# 84_PCIE-PCIE3_0_1x4Lanes_RC_64P.net
KiCad netlist of a schematic drawn in Altium Designer
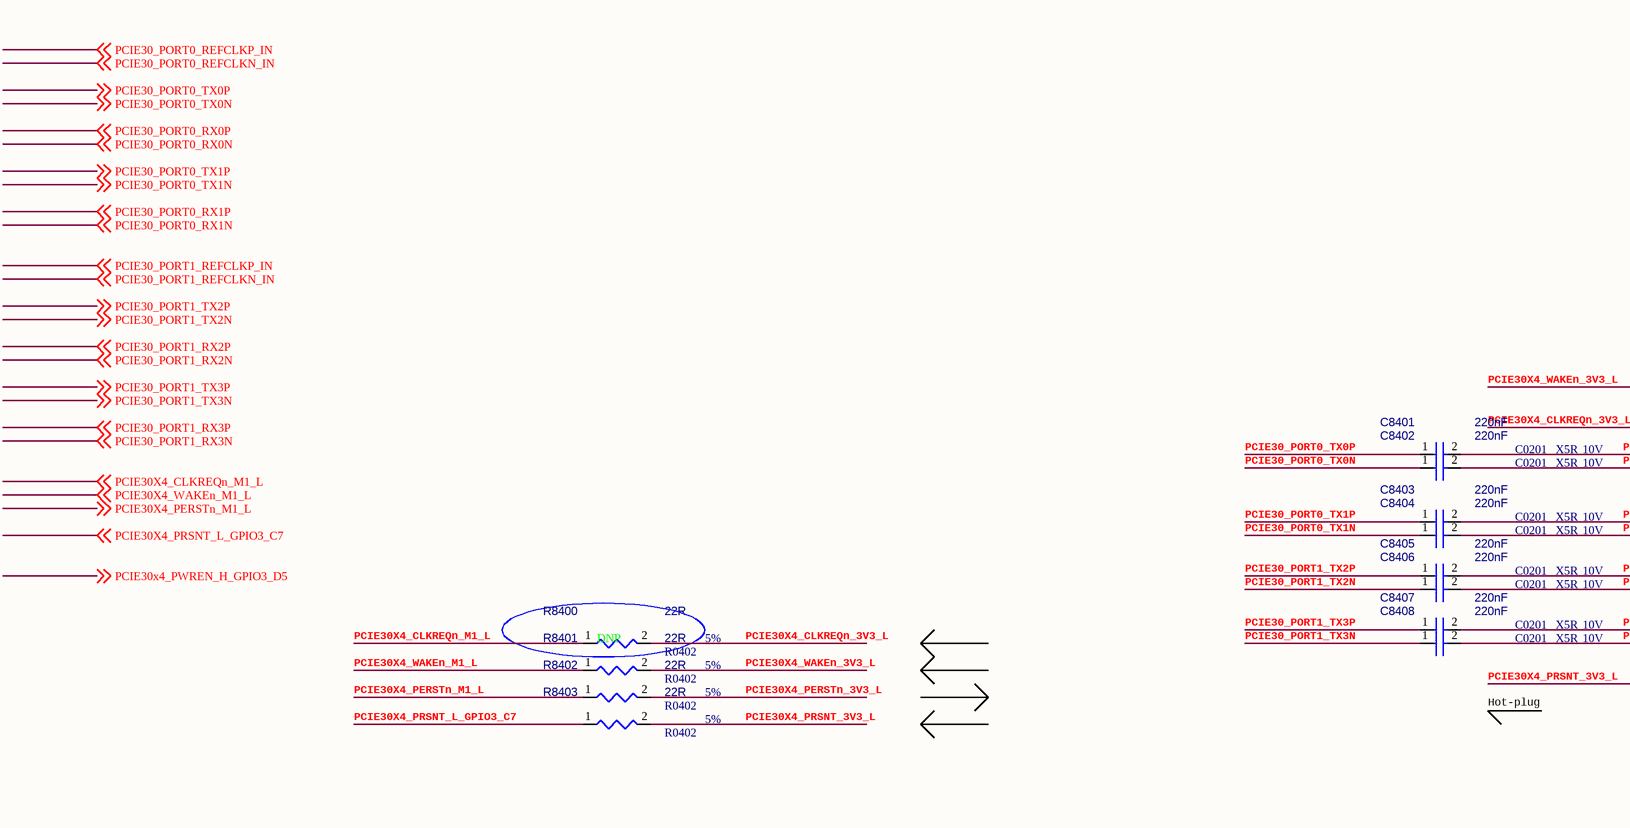
[diagram p0: 84.PCIE-PCIE3.0_1x4Lanes_RC_64P.SchDoc, top left]
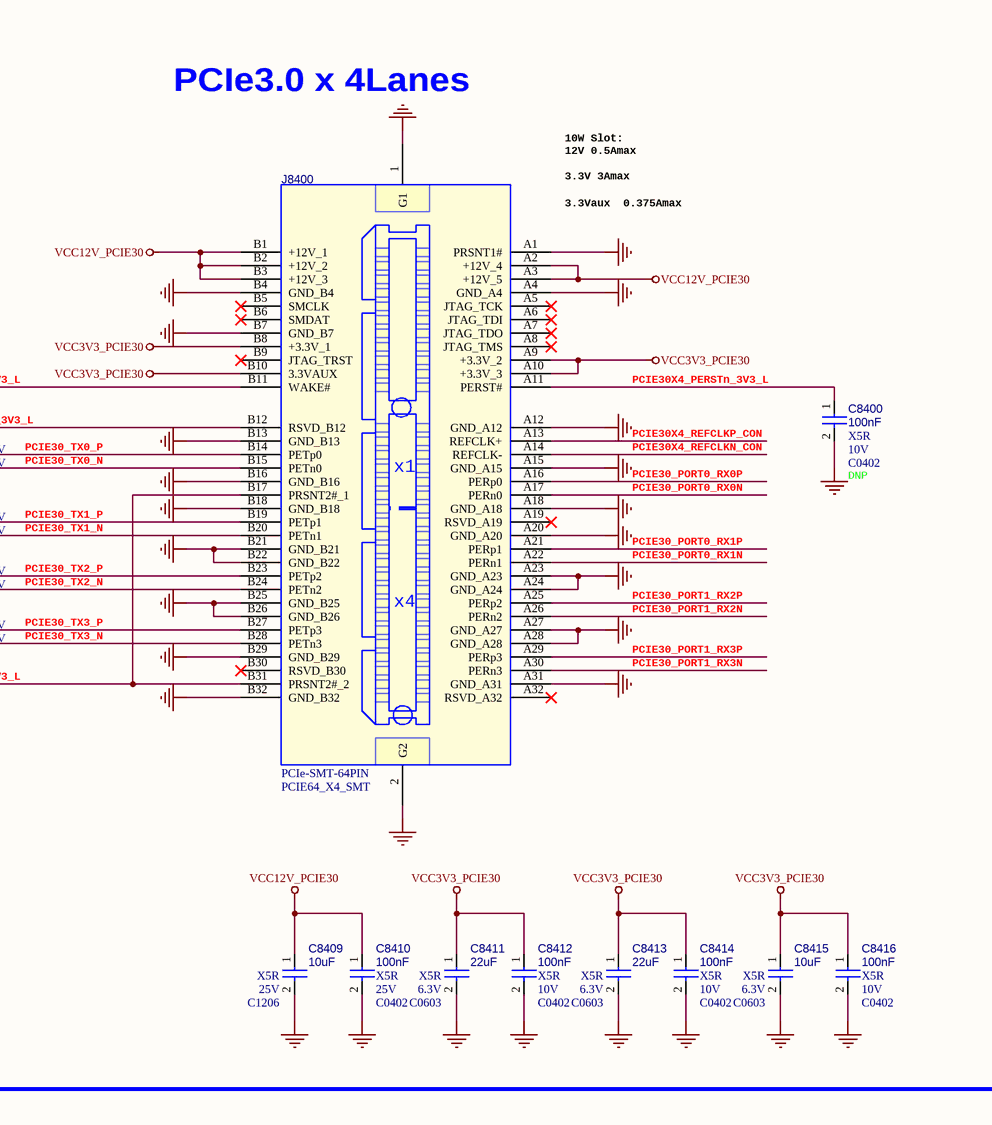
[diagram p1: 84.PCIE-PCIE3.0_1x4Lanes_RC_64P.SchDoc, top right]
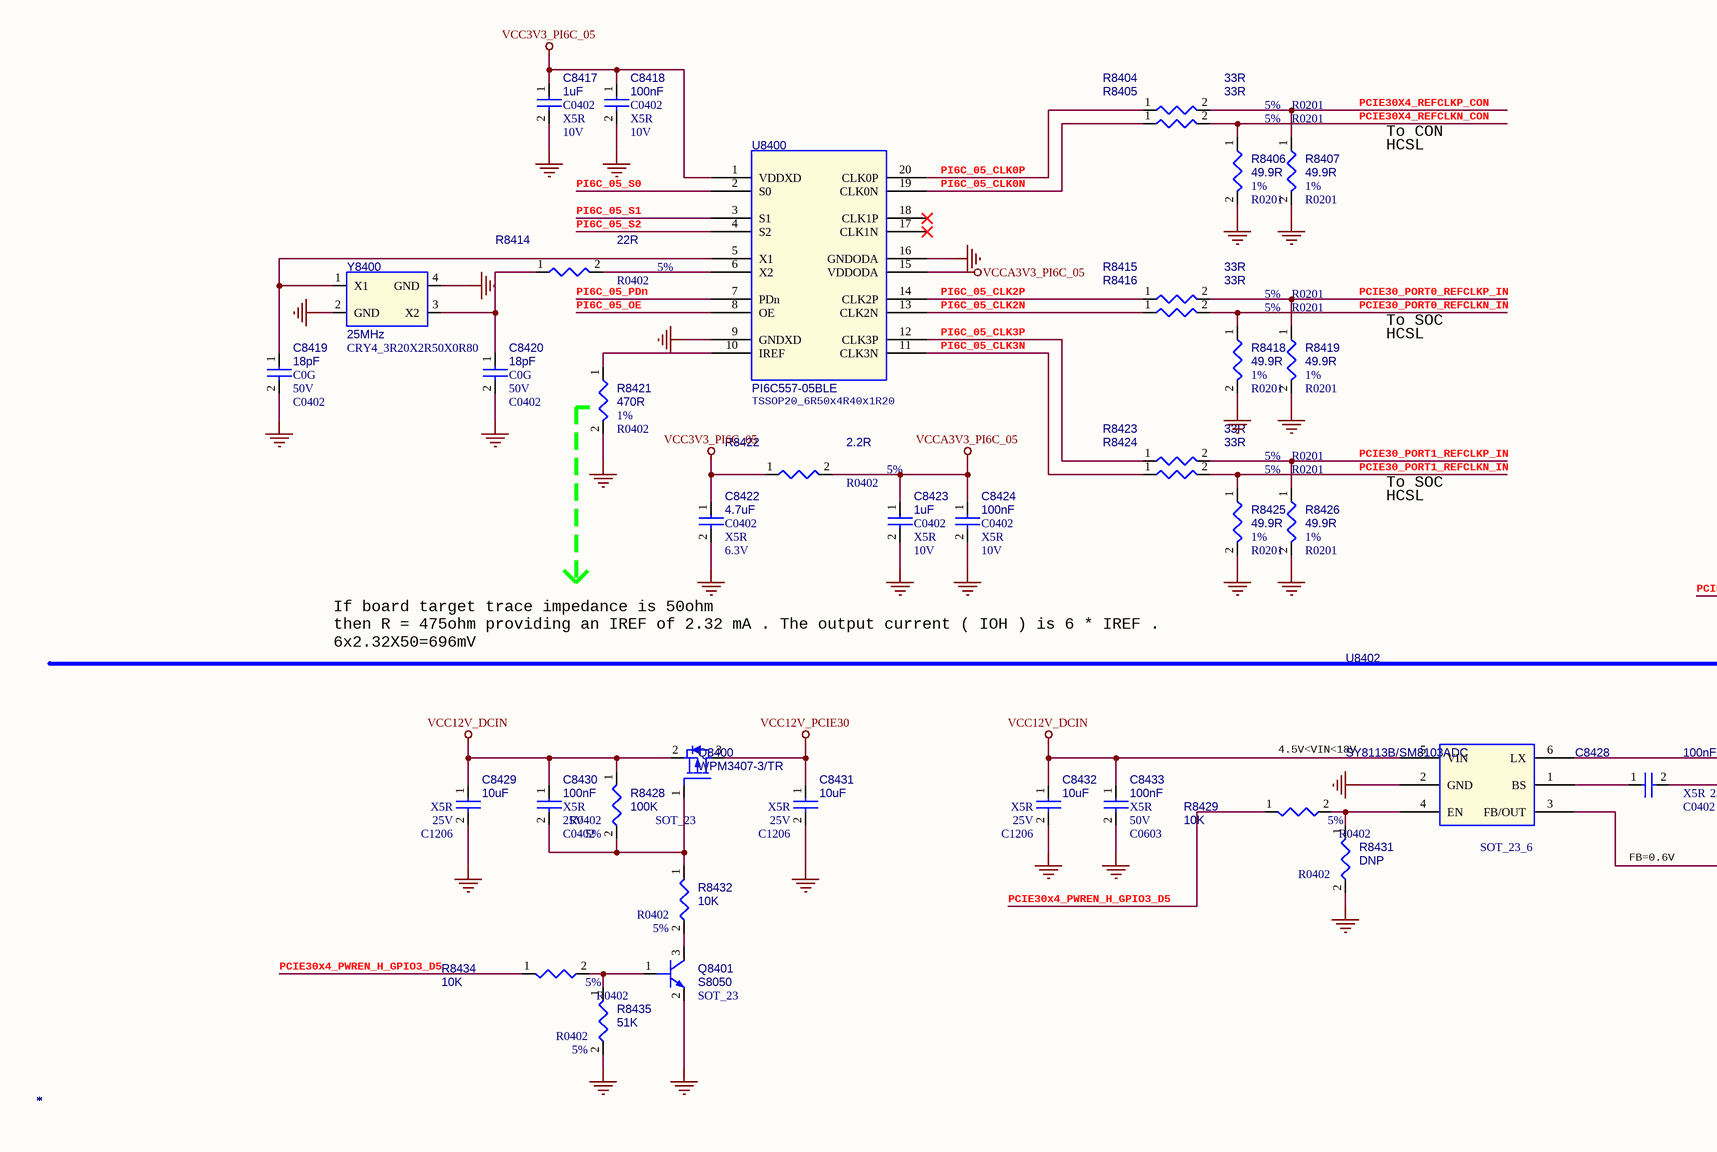
[diagram p2: 84.PCIE-PCIE3.0_1x4Lanes_RC_64P.SchDoc, bottom left]
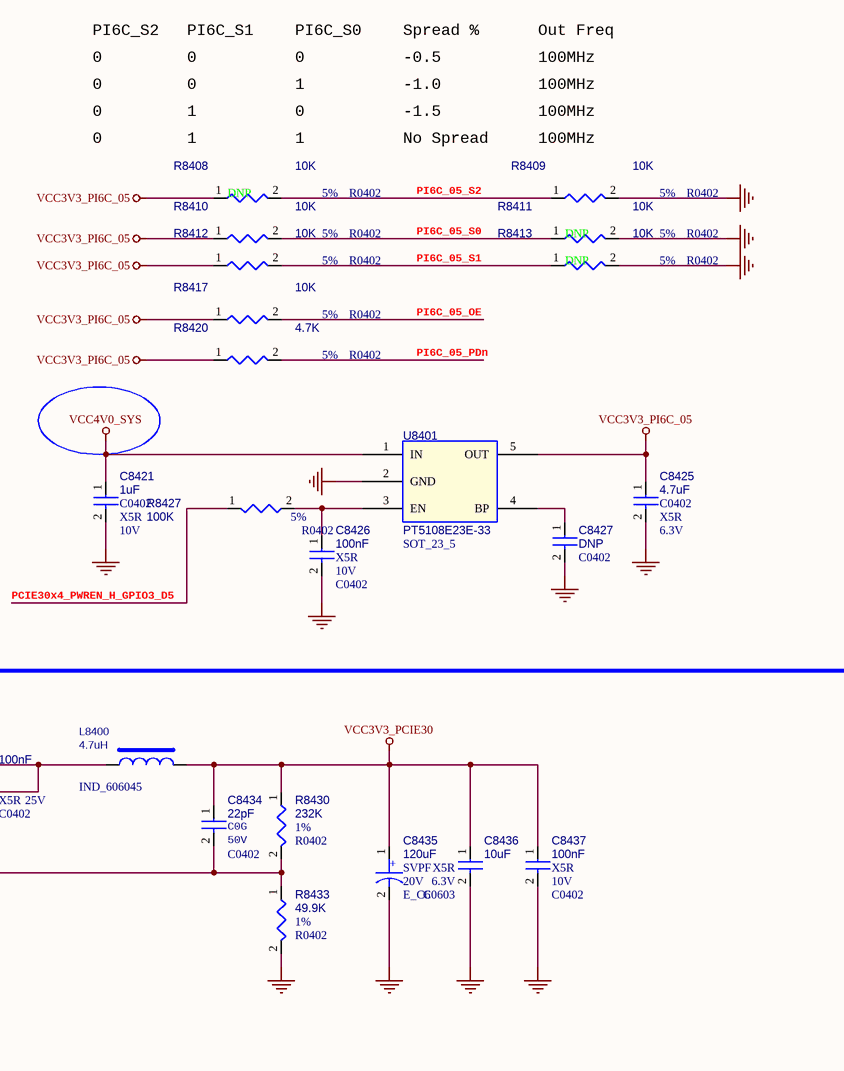
[diagram p3: 84.PCIE-PCIE3.0_1x4Lanes_RC_64P.SchDoc, bottom right]

(export (version "E")
  (design (tool "Eeschema 10.0.6"))
  (components
    (comp (ref "C8400")
      (value "*")
      (footprint "C0402")
      (description "cap,100.00nF,+/-10%,10V,X5R,C0402")
      (fields
        (field (name "VOLTAGE") "10V")
        (field (name "PCB FOOTPRINT") "C0402")
        (field (name "DIELECTRIC") "X5R")
        (field (name "TOLERANCE") "10%")
        (field (name "MANUFACTURER") "TDK")
        (field (name "OPTION") "DNP")
        (field (name "ALTIUM_UNNAMED_1") "100nF")
        (field (name "CREATED BY") "JJJ")
      )
      (libsource (lib "*") (part "CAP NP"))
    )
    (comp (ref "C8401")
      (value "*")
      (footprint "C0201")
      (description "cap,220.00nF,+/-10%,10V,X5R,C0201")
      (fields
        (field (name "VOLTAGE") "10V")
        (field (name "PCB FOOTPRINT") "C0201")
        (field (name "DIELECTRIC") "X5R")
        (field (name "MANUFACTURER") "TDK")
        (field (name "TOLERANCE") "10%")
        (field (name "ALTIUM_UNNAMED_1") "220nF")
        (field (name "CREATED BY") "JJJ")
      )
      (libsource (lib "*") (part "CAP NP"))
    )
    (comp (ref "C8402")
      (value "*")
      (footprint "C0201")
      (description "cap,220.00nF,+/-10%,10V,X5R,C0201")
      (fields
        (field (name "VOLTAGE") "10V")
        (field (name "PCB FOOTPRINT") "C0201")
        (field (name "DIELECTRIC") "X5R")
        (field (name "MANUFACTURER") "TDK")
        (field (name "TOLERANCE") "10%")
        (field (name "ALTIUM_UNNAMED_1") "220nF")
        (field (name "CREATED BY") "JJJ")
      )
      (libsource (lib "*") (part "CAP NP"))
    )
    (comp (ref "C8403")
      (value "*")
      (footprint "C0201")
      (description "cap,220.00nF,+/-10%,10V,X5R,C0201")
      (fields
        (field (name "VOLTAGE") "10V")
        (field (name "PCB FOOTPRINT") "C0201")
        (field (name "DIELECTRIC") "X5R")
        (field (name "MANUFACTURER") "TDK")
        (field (name "TOLERANCE") "10%")
        (field (name "ALTIUM_UNNAMED_1") "220nF")
        (field (name "CREATED BY") "JJJ")
      )
      (libsource (lib "*") (part "CAP NP"))
    )
    (comp (ref "C8404")
      (value "*")
      (footprint "C0201")
      (description "cap,220.00nF,+/-10%,10V,X5R,C0201")
      (fields
        (field (name "VOLTAGE") "10V")
        (field (name "PCB FOOTPRINT") "C0201")
        (field (name "DIELECTRIC") "X5R")
        (field (name "MANUFACTURER") "TDK")
        (field (name "TOLERANCE") "10%")
        (field (name "ALTIUM_UNNAMED_1") "220nF")
        (field (name "CREATED BY") "JJJ")
      )
      (libsource (lib "*") (part "CAP NP"))
    )
    (comp (ref "C8405")
      (value "*")
      (footprint "C0201")
      (description "cap,220.00nF,+/-10%,10V,X5R,C0201")
      (fields
        (field (name "VOLTAGE") "10V")
        (field (name "PCB FOOTPRINT") "C0201")
        (field (name "DIELECTRIC") "X5R")
        (field (name "MANUFACTURER") "TDK")
        (field (name "TOLERANCE") "10%")
        (field (name "ALTIUM_UNNAMED_1") "220nF")
        (field (name "CREATED BY") "JJJ")
      )
      (libsource (lib "*") (part "CAP NP"))
    )
    (comp (ref "C8406")
      (value "*")
      (footprint "C0201")
      (description "cap,220.00nF,+/-10%,10V,X5R,C0201")
      (fields
        (field (name "VOLTAGE") "10V")
        (field (name "PCB FOOTPRINT") "C0201")
        (field (name "DIELECTRIC") "X5R")
        (field (name "MANUFACTURER") "TDK")
        (field (name "TOLERANCE") "10%")
        (field (name "ALTIUM_UNNAMED_1") "220nF")
        (field (name "CREATED BY") "JJJ")
      )
      (libsource (lib "*") (part "CAP NP"))
    )
    (comp (ref "C8407")
      (value "*")
      (footprint "C0201")
      (description "cap,220.00nF,+/-10%,10V,X5R,C0201")
      (fields
        (field (name "VOLTAGE") "10V")
        (field (name "PCB FOOTPRINT") "C0201")
        (field (name "DIELECTRIC") "X5R")
        (field (name "MANUFACTURER") "TDK")
        (field (name "TOLERANCE") "10%")
        (field (name "ALTIUM_UNNAMED_1") "220nF")
        (field (name "CREATED BY") "JJJ")
      )
      (libsource (lib "*") (part "CAP NP"))
    )
    (comp (ref "C8408")
      (value "*")
      (footprint "C0201")
      (description "cap,220.00nF,+/-10%,10V,X5R,C0201")
      (fields
        (field (name "VOLTAGE") "10V")
        (field (name "PCB FOOTPRINT") "C0201")
        (field (name "DIELECTRIC") "X5R")
        (field (name "MANUFACTURER") "TDK")
        (field (name "TOLERANCE") "10%")
        (field (name "ALTIUM_UNNAMED_1") "220nF")
        (field (name "CREATED BY") "JJJ")
      )
      (libsource (lib "*") (part "CAP NP"))
    )
    (comp (ref "C8409")
      (value "*")
      (footprint "C1206")
      (description "cap,10.00uF,+/-10%,25V,X5R,C1206")
      (fields
        (field (name "VOLTAGE") "25V")
        (field (name "PCB FOOTPRINT") "C1206")
        (field (name "DIELECTRIC") "X5R")
        (field (name "MANUFACTURER") "TDK")
        (field (name "TOLERANCE") "10%")
        (field (name "ALTIUM_UNNAMED_1") "10uF")
        (field (name "CREATED BY") "JJJ")
      )
      (libsource (lib "*") (part "CAP NP"))
    )
    (comp (ref "C8410")
      (value "*")
      (footprint "C0402")
      (description "cap,100.00nF,+/-10%,25V,X5R,C0402")
      (fields
        (field (name "VOLTAGE") "25V")
        (field (name "PCB FOOTPRINT") "C0402")
        (field (name "DIELECTRIC") "X5R")
        (field (name "TOLERANCE") "10%")
        (field (name "MANUFACTURER") "TDK")
        (field (name "ALTIUM_UNNAMED_1") "100nF")
        (field (name "CREATED BY") "JJJ")
      )
      (libsource (lib "*") (part "CAP NP"))
    )
    (comp (ref "C8411")
      (value "*")
      (footprint "C0603")
      (description "cap,22.00uF,+/-20%,6.3V,X5R,C0603")
      (fields
        (field (name "VOLTAGE") "6.3V")
        (field (name "PCB FOOTPRINT") "C0603")
        (field (name "DIELECTRIC") "X5R")
        (field (name "MANUFACTURER") "TDK")
        (field (name "TOLERANCE") "20%")
        (field (name "ALTIUM_UNNAMED_1") "22uF")
        (field (name "CREATED BY") "JJJ")
      )
      (libsource (lib "*") (part "CAP NP"))
    )
    (comp (ref "C8412")
      (value "*")
      (footprint "C0402")
      (description "cap,100.00nF,+/-10%,10V,X5R,C0402")
      (fields
        (field (name "VOLTAGE") "10V")
        (field (name "PCB FOOTPRINT") "C0402")
        (field (name "DIELECTRIC") "X5R")
        (field (name "MANUFACTURER") "TDK")
        (field (name "TOLERANCE") "10%")
        (field (name "ALTIUM_UNNAMED_1") "100nF")
        (field (name "CREATED BY") "JJJ")
      )
      (libsource (lib "*") (part "CAP NP"))
    )
    (comp (ref "C8413")
      (value "*")
      (footprint "C0603")
      (description "cap,22.00uF,+/-20%,6.3V,X5R,C0603")
      (fields
        (field (name "VOLTAGE") "6.3V")
        (field (name "PCB FOOTPRINT") "C0603")
        (field (name "DIELECTRIC") "X5R")
        (field (name "MANUFACTURER") "TDK")
        (field (name "TOLERANCE") "20%")
        (field (name "ALTIUM_UNNAMED_1") "22uF")
        (field (name "CREATED BY") "JJJ")
      )
      (libsource (lib "*") (part "CAP NP"))
    )
    (comp (ref "C8414")
      (value "*")
      (footprint "C0402")
      (description "cap,100.00nF,+/-10%,10V,X5R,C0402")
      (fields
        (field (name "VOLTAGE") "10V")
        (field (name "PCB FOOTPRINT") "C0402")
        (field (name "DIELECTRIC") "X5R")
        (field (name "MANUFACTURER") "TDK")
        (field (name "TOLERANCE") "10%")
        (field (name "ALTIUM_UNNAMED_1") "100nF")
        (field (name "CREATED BY") "JJJ")
      )
      (libsource (lib "*") (part "CAP NP"))
    )
    (comp (ref "C8415")
      (value "*")
      (footprint "C0603")
      (description "cap,10.00uF,+/-10%,6.3V,X5R,C0603")
      (fields
        (field (name "VOLTAGE") "6.3V")
        (field (name "PCB FOOTPRINT") "C0603")
        (field (name "DIELECTRIC") "X5R")
        (field (name "TOLERANCE") "10%")
        (field (name "MANUFACTURER") "TDK")
        (field (name "ALTIUM_UNNAMED_1") "10uF")
        (field (name "CREATED BY") "JJJ")
      )
      (libsource (lib "*") (part "CAP NP"))
    )
    (comp (ref "C8416")
      (value "*")
      (footprint "C0402")
      (description "cap,100.00nF,+/-10%,10V,X5R,C0402")
      (fields
        (field (name "VOLTAGE") "10V")
        (field (name "PCB FOOTPRINT") "C0402")
        (field (name "DIELECTRIC") "X5R")
        (field (name "TOLERANCE") "10%")
        (field (name "MANUFACTURER") "TDK")
        (field (name "ALTIUM_UNNAMED_1") "100nF")
        (field (name "CREATED BY") "JJJ")
      )
      (libsource (lib "*") (part "CAP NP"))
    )
    (comp (ref "C8417")
      (value "*")
      (footprint "C0402")
      (description "cap,1.00uF,+/-10%,10V,X5R,C0402")
      (fields
        (field (name "VOLTAGE") "10V")
        (field (name "PCB FOOTPRINT") "C0402")
        (field (name "DIELECTRIC") "X5R")
        (field (name "MANUFACTURER") "TDK")
        (field (name "TOLERANCE") "10%")
        (field (name "ALTIUM_UNNAMED_1") "1uF")
        (field (name "CREATED BY") "JJJ")
      )
      (libsource (lib "*") (part "CAP NP"))
    )
    (comp (ref "C8418")
      (value "*")
      (footprint "C0402")
      (description "cap,100.00nF,+/-10%,10V,X5R,C0402")
      (fields
        (field (name "VOLTAGE") "10V")
        (field (name "PCB FOOTPRINT") "C0402")
        (field (name "DIELECTRIC") "X5R")
        (field (name "TOLERANCE") "10%")
        (field (name "MANUFACTURER") "TDK")
        (field (name "ALTIUM_UNNAMED_1") "100nF")
        (field (name "CREATED BY") "JJJ")
      )
      (libsource (lib "*") (part "CAP NP"))
    )
    (comp (ref "C8419")
      (value "*")
      (footprint "C0402")
      (description "cap,18.00pF,+/-5%,50V,C0G,C0402")
      (fields
        (field (name "VOLTAGE") "50V")
        (field (name "PCB FOOTPRINT") "C0402")
        (field (name "DIELECTRIC") "C0G")
        (field (name "TOLERANCE") "5%")
        (field (name "MANUFACTURER") "TDK")
        (field (name "ALTIUM_UNNAMED_1") "18pF")
        (field (name "CREATED BY") "JJJ")
      )
      (libsource (lib "*") (part "CAP NP"))
    )
    (comp (ref "C8420")
      (value "*")
      (footprint "C0402")
      (description "cap,18.00pF,+/-5%,50V,C0G,C0402")
      (fields
        (field (name "VOLTAGE") "50V")
        (field (name "PCB FOOTPRINT") "C0402")
        (field (name "DIELECTRIC") "C0G")
        (field (name "MANUFACTURER") "TDK")
        (field (name "TOLERANCE") "5%")
        (field (name "ALTIUM_UNNAMED_1") "18pF")
        (field (name "CREATED BY") "JJJ")
      )
      (libsource (lib "*") (part "CAP NP"))
    )
    (comp (ref "C8421")
      (value "*")
      (footprint "C0402")
      (description "cap,1.00uF,+/-10%,10V,X5R,C0402")
      (fields
        (field (name "VOLTAGE") "10V")
        (field (name "PCB FOOTPRINT") "C0402")
        (field (name "DIELECTRIC") "X5R")
        (field (name "TOLERANCE") "10%")
        (field (name "MANUFACTURER") "TDK")
        (field (name "ALTIUM_UNNAMED_1") "1uF")
        (field (name "CREATED BY") "JJJ")
      )
      (libsource (lib "*") (part "CAP NP"))
    )
    (comp (ref "C8422")
      (value "*")
      (footprint "C0402")
      (description "cap,4.70uF,+/-10%,6.3V,X5R,C0402")
      (fields
        (field (name "VOLTAGE") "6.3V")
        (field (name "PCB FOOTPRINT") "C0402")
        (field (name "DIELECTRIC") "X5R")
        (field (name "TOLERANCE") "10%")
        (field (name "MANUFACTURER") "TDK")
        (field (name "ALTIUM_UNNAMED_1") "4.7uF")
        (field (name "CREATED BY") "JJJ")
      )
      (libsource (lib "*") (part "CAP NP"))
    )
    (comp (ref "C8423")
      (value "*")
      (footprint "C0402")
      (description "cap,1.00uF,+/-10%,10V,X5R,C0402")
      (fields
        (field (name "VOLTAGE") "10V")
        (field (name "PCB FOOTPRINT") "C0402")
        (field (name "DIELECTRIC") "X5R")
        (field (name "MANUFACTURER") "TDK")
        (field (name "TOLERANCE") "10%")
        (field (name "ALTIUM_UNNAMED_1") "1uF")
        (field (name "CREATED BY") "JJJ")
      )
      (libsource (lib "*") (part "CAP NP"))
    )
    (comp (ref "C8424")
      (value "*")
      (footprint "C0402")
      (description "cap,100.00nF,+/-10%,10V,X5R,C0402")
      (fields
        (field (name "VOLTAGE") "10V")
        (field (name "PCB FOOTPRINT") "C0402")
        (field (name "DIELECTRIC") "X5R")
        (field (name "TOLERANCE") "10%")
        (field (name "MANUFACTURER") "TDK")
        (field (name "ALTIUM_UNNAMED_1") "100nF")
        (field (name "CREATED BY") "JJJ")
      )
      (libsource (lib "*") (part "CAP NP"))
    )
    (comp (ref "C8425")
      (value "*")
      (footprint "C0402")
      (description "cap,4.70uF,+/-10%,6.3V,X5R,C0402")
      (fields
        (field (name "VOLTAGE") "6.3V")
        (field (name "PCB FOOTPRINT") "C0402")
        (field (name "DIELECTRIC") "X5R")
        (field (name "MANUFACTURER") "TDK")
        (field (name "TOLERANCE") "10%")
        (field (name "ALTIUM_UNNAMED_1") "4.7uF")
        (field (name "CREATED BY") "JJJ")
      )
      (libsource (lib "*") (part "CAP NP"))
    )
    (comp (ref "C8426")
      (value "*")
      (footprint "C0402")
      (description "cap,100.00nF,+/-10%,10V,X5R,C0402")
      (fields
        (field (name "VOLTAGE") "10V")
        (field (name "PCB FOOTPRINT") "C0402")
        (field (name "DIELECTRIC") "X5R")
        (field (name "TOLERANCE") "10%")
        (field (name "MANUFACTURER") "TDK")
        (field (name "ALTIUM_UNNAMED_1") "100nF")
        (field (name "CREATED BY") "JJJ")
      )
      (libsource (lib "*") (part "CAP NP"))
    )
    (comp (ref "C8427")
      (value "*")
      (footprint "C0402")
      (description "Did Not Place.")
      (fields
        (field (name "PCB FOOTPRINT") "C0402")
        (field (name "ALTIUM_UNNAMED_1") "DNP")
        (field (name "CREATED BY") "JJJ")
      )
      (libsource (lib "*") (part "CAP NP"))
    )
    (comp (ref "C8428")
      (value "*")
      (footprint "C0402")
      (description "cap,100.00nF,+/-10%,25V,X5R,C0402")
      (fields
        (field (name "VOLTAGE") "25V")
        (field (name "PCB FOOTPRINT") "C0402")
        (field (name "DIELECTRIC") "X5R")
        (field (name "TOLERANCE") "10%")
        (field (name "MANUFACTURER") "TDK")
        (field (name "ALTIUM_UNNAMED_1") "100nF")
        (field (name "CREATED BY") "JJJ")
      )
      (libsource (lib "*") (part "CAP NP"))
    )
    (comp (ref "C8429")
      (value "*")
      (footprint "C1206")
      (description "cap,10.00uF,+/-10%,25V,X5R,C1206")
      (fields
        (field (name "VOLTAGE") "25V")
        (field (name "PCB FOOTPRINT") "C1206")
        (field (name "DIELECTRIC") "X5R")
        (field (name "TOLERANCE") "10%")
        (field (name "MANUFACTURER") "TDK")
        (field (name "ALTIUM_UNNAMED_1") "10uF")
        (field (name "CREATED BY") "JJJ")
      )
      (libsource (lib "*") (part "CAP NP"))
    )
    (comp (ref "C8430")
      (value "*")
      (footprint "C0402")
      (description "cap,100.00nF,+/-10%,25V,X5R,C0402")
      (fields
        (field (name "VOLTAGE") "25V")
        (field (name "PCB FOOTPRINT") "C0402")
        (field (name "DIELECTRIC") "X5R")
        (field (name "MANUFACTURER") "TDK")
        (field (name "TOLERANCE") "10%")
        (field (name "ALTIUM_UNNAMED_1") "100nF")
        (field (name "CREATED BY") "JJJ")
      )
      (libsource (lib "*") (part "CAP NP"))
    )
    (comp (ref "C8431")
      (value "*")
      (footprint "C1206")
      (description "cap,10.00uF,+/-10%,25V,X5R,C1206")
      (fields
        (field (name "VOLTAGE") "25V")
        (field (name "PCB FOOTPRINT") "C1206")
        (field (name "DIELECTRIC") "X5R")
        (field (name "TOLERANCE") "10%")
        (field (name "MANUFACTURER") "TDK")
        (field (name "ALTIUM_UNNAMED_1") "10uF")
        (field (name "CREATED BY") "JJJ")
      )
      (libsource (lib "*") (part "CAP NP"))
    )
    (comp (ref "C8432")
      (value "*")
      (footprint "C1206")
      (description "cap,10.00uF,+/-10%,25V,X5R,C1206")
      (fields
        (field (name "VOLTAGE") "25V")
        (field (name "PCB FOOTPRINT") "C1206")
        (field (name "DIELECTRIC") "X5R")
        (field (name "MANUFACTURER") "TDK")
        (field (name "TOLERANCE") "10%")
        (field (name "ALTIUM_UNNAMED_1") "10uF")
        (field (name "CREATED BY") "JJJ")
      )
      (libsource (lib "*") (part "CAP NP"))
    )
    (comp (ref "C8433")
      (value "*")
      (footprint "C0603")
      (description "cap,100.00nF,+/-10%,50V,X5R,C0603")
      (fields
        (field (name "VOLTAGE") "50V")
        (field (name "PCB FOOTPRINT") "C0603")
        (field (name "DIELECTRIC") "X5R")
        (field (name "MANUFACTURER") "TDK")
        (field (name "TOLERANCE") "10%")
        (field (name "ALTIUM_UNNAMED_1") "100nF")
        (field (name "CREATED BY") "JJJ")
      )
      (libsource (lib "*") (part "CAP NP"))
    )
    (comp (ref "C8434")
      (value "*")
      (footprint "C0402")
      (description "cap,22.00pF,+/-5%,50V,C0G,C0402")
      (fields
        (field (name "VOLTAGE") "50V")
        (field (name "PCB FOOTPRINT") "C0402")
        (field (name "DIELECTRIC") "C0G")
        (field (name "TOLERANCE") "5%")
        (field (name "MANUFACTURER") "TDK")
        (field (name "ALTIUM_UNNAMED_1") "22pF")
        (field (name "CREATED BY") "JJJ")
      )
      (libsource (lib "*") (part "CAP NP"))
    )
    (comp (ref "C8435")
      (value "*")
      (footprint "E_C6")
      (description "120uF,20V,25mR,SVPF")
      (fields
        (field (name "VOLTAGE") "20V")
        (field (name "DIELECTRIC") "SVPF")
        (field (name "PCB FOOTPRINT") "E_C6")
        (field (name "MANUFACTURER") "Panasonic")
        (field (name "TOLERANCE") "20%")
        (field (name "ALTIUM_UNNAMED_1") "120uF")
        (field (name "CREATED BY") "JJJ")
      )
      (libsource (lib "*") (part "CAP"))
    )
    (comp (ref "C8436")
      (value "*")
      (footprint "C0603")
      (description "cap,10.00uF,+/-10%,6.3V,X5R,C0603")
      (fields
        (field (name "VOLTAGE") "6.3V")
        (field (name "PCB FOOTPRINT") "C0603")
        (field (name "DIELECTRIC") "X5R")
        (field (name "TOLERANCE") "10%")
        (field (name "MANUFACTURER") "TDK")
        (field (name "ALTIUM_UNNAMED_1") "10uF")
        (field (name "CREATED BY") "JJJ")
      )
      (libsource (lib "*") (part "CAP NP"))
    )
    (comp (ref "C8437")
      (value "*")
      (footprint "C0402")
      (description "cap,100.00nF,+/-10%,10V,X5R,C0402")
      (fields
        (field (name "VOLTAGE") "10V")
        (field (name "PCB FOOTPRINT") "C0402")
        (field (name "DIELECTRIC") "X5R")
        (field (name "MANUFACTURER") "TDK")
        (field (name "TOLERANCE") "10%")
        (field (name "ALTIUM_UNNAMED_1") "100nF")
        (field (name "CREATED BY") "JJJ")
      )
      (libsource (lib "*") (part "CAP NP"))
    )
    (comp (ref "J8400")
      (value "*")
      (footprint "PCIE64_X4_SMT")
      (fields
        (field (name "PCB FOOTPRINT") "PCIE64_X4_SMT")
        (field (name "ALTIUM_UNNAMED_1") "PCIe-SMT-64PIN")
      )
      (libsource (lib "*") (part "PCIeX4_1"))
    )
    (comp (ref "L8400")
      (value "*")
      (footprint "IND_606045")
      (description "Power Inductor,4.7uH,0.2,IND_606045")
      (fields
        (field (name "PCB FOOTPRINT") "IND_606045")
        (field (name "MANUFACTURER") "sunlord")
        (field (name "TOLERANCE") "20%")
        (field (name "ALTIUM_UNNAMED_1") "4.7uH")
        (field (name "CREATED BY") "YWQ")
      )
      (libsource (lib "*") (part "INDUCTORS OF FERRITE_Dup1"))
    )
    (comp (ref "Q8400")
      (value "*")
      (footprint "SOT23")
      (description "PMOS,WPM3407-3/TR,SOT_23,Id=4.4A,Vds=30V")
      (fields
        (field (name "PCB FOOTPRINT") "SOT_23")
        (field (name "MANUFACTURER") "WillSemi(О¤¶ы°лµјМе)")
        (field (name "ALTIUM_UNNAMED_1") "WPM3407-3/TR")
        (field (name "CREATED BY") "JJJ")
      )
      (libsource (lib "*") (part "MOSFET P"))
    )
    (comp (ref "Q8401")
      (value "*")
      (footprint "SOT_23")
      (description "S8050,SOT23")
      (fields
        (field (name "PCB FOOTPRINT") "SOT_23")
        (field (name "MANUFACTURER") "і¤µз")
        (field (name "ALTIUM_UNNAMED_1") "S8050")
        (field (name "CREATED BY") "JJJ")
      )
      (libsource (lib "*") (part "NPN"))
    )
    (comp (ref "R8400")
      (value "*")
      (footprint "R0402")
      (description "НЁУГєсД¤µзЧи,22R,+/-5%,R0402,1/16W.")
      (fields
        (field (name "PCB FOOTPRINT") "R0402")
        (field (name "TOLERANCE") "5%")
        (field (name "MANUFACTURER") "YAGEO")
        (field (name "OPTION") "DNP")
        (field (name "ALTIUM_UNNAMED_1") "22R")
        (field (name "CREATED BY") "YTL")
      )
      (libsource (lib "*") (part "RESISTOR_Dup1"))
    )
    (comp (ref "R8401")
      (value "*")
      (footprint "R0402")
      (description "НЁУГєсД¤µзЧи,22R,+/-5%,R0402,1/16W.")
      (fields
        (field (name "PCB FOOTPRINT") "R0402")
        (field (name "TOLERANCE") "5%")
        (field (name "MANUFACTURER") "YAGEO")
        (field (name "ALTIUM_UNNAMED_1") "22R")
        (field (name "CREATED BY") "YTL")
      )
      (libsource (lib "*") (part "RESISTOR_Dup1"))
    )
    (comp (ref "R8402")
      (value "*")
      (footprint "R0402")
      (description "НЁУГєсД¤µзЧи,22R,+/-5%,R0402,1/16W.")
      (fields
        (field (name "PCB FOOTPRINT") "R0402")
        (field (name "TOLERANCE") "5%")
        (field (name "MANUFACTURER") "YAGEO")
        (field (name "ALTIUM_UNNAMED_1") "22R")
        (field (name "CREATED BY") "YTL")
      )
      (libsource (lib "*") (part "RESISTOR_Dup1"))
    )
    (comp (ref "R8403")
      (value "*")
      (footprint "R0402")
      (description "НЁУГєсД¤µзЧи,22R,+/-5%,R0402,1/16W.")
      (fields
        (field (name "PCB FOOTPRINT") "R0402")
        (field (name "TOLERANCE") "5%")
        (field (name "MANUFACTURER") "YAGEO")
        (field (name "ALTIUM_UNNAMED_1") "22R")
        (field (name "CREATED BY") "YTL")
      )
      (libsource (lib "*") (part "RESISTOR_Dup1"))
    )
    (comp (ref "R8404")
      (value "*")
      (footprint "R0402")
      (description "НЁУГєсД¤µзЧи,33R,+/-5%,R0201,1/20W.")
      (fields
        (field (name "PCB FOOTPRINT") "R0201")
        (field (name "TOLERANCE") "5%")
        (field (name "MANUFACTURER") "YAGEO")
        (field (name "ALTIUM_UNNAMED_1") "33R")
        (field (name "CREATED BY") "YTL")
      )
      (libsource (lib "*") (part "RESISTOR_Dup1"))
    )
    (comp (ref "R8405")
      (value "*")
      (footprint "R0402")
      (description "НЁУГєсД¤µзЧи,33R,+/-5%,R0201,1/20W.")
      (fields
        (field (name "PCB FOOTPRINT") "R0201")
        (field (name "TOLERANCE") "5%")
        (field (name "MANUFACTURER") "YAGEO")
        (field (name "ALTIUM_UNNAMED_1") "33R")
        (field (name "CREATED BY") "YTL")
      )
      (libsource (lib "*") (part "RESISTOR_Dup1"))
    )
    (comp (ref "R8406")
      (value "*")
      (footprint "R0402")
      (description "НЁУГєсД¤µзЧи,49R9,+/-1%,R0201,1/20W.")
      (fields
        (field (name "PCB FOOTPRINT") "R0201")
        (field (name "TOLERANCE") "1%")
        (field (name "MANUFACTURER") "YAGEO")
        (field (name "ALTIUM_UNNAMED_1") "49.9R")
        (field (name "CREATED BY") "YTL")
      )
      (libsource (lib "*") (part "RESISTOR_Dup1"))
    )
    (comp (ref "R8407")
      (value "*")
      (footprint "R0402")
      (description "НЁУГєсД¤µзЧи,49R9,+/-1%,R0201,1/20W.")
      (fields
        (field (name "PCB FOOTPRINT") "R0201")
        (field (name "TOLERANCE") "1%")
        (field (name "MANUFACTURER") "YAGEO")
        (field (name "ALTIUM_UNNAMED_1") "49.9R")
        (field (name "CREATED BY") "YTL")
      )
      (libsource (lib "*") (part "RESISTOR_Dup1"))
    )
    (comp (ref "R8408")
      (value "*")
      (footprint "R0402")
      (description "НЁУГєсД¤µзЧи,10K,+/-5%,R0402,1/16W.")
      (fields
        (field (name "PCB FOOTPRINT") "R0402")
        (field (name "TOLERANCE") "5%")
        (field (name "MANUFACTURER") "YAGEO")
        (field (name "OPTION") "DNP")
        (field (name "ALTIUM_UNNAMED_1") "10K")
        (field (name "CREATED BY") "YTL")
      )
      (libsource (lib "*") (part "RESISTOR_Dup1"))
    )
    (comp (ref "R8409")
      (value "*")
      (footprint "R0402")
      (description "НЁУГєсД¤µзЧи,10K,+/-5%,R0402,1/16W.")
      (fields
        (field (name "PCB FOOTPRINT") "R0402")
        (field (name "TOLERANCE") "5%")
        (field (name "MANUFACTURER") "YAGEO")
        (field (name "ALTIUM_UNNAMED_1") "10K")
        (field (name "CREATED BY") "YTL")
      )
      (libsource (lib "*") (part "RESISTOR_Dup1"))
    )
    (comp (ref "R8410")
      (value "*")
      (footprint "R0402")
      (description "НЁУГєсД¤µзЧи,10K,+/-5%,R0402,1/16W.")
      (fields
        (field (name "PCB FOOTPRINT") "R0402")
        (field (name "TOLERANCE") "5%")
        (field (name "MANUFACTURER") "YAGEO")
        (field (name "ALTIUM_UNNAMED_1") "10K")
        (field (name "CREATED BY") "YTL")
      )
      (libsource (lib "*") (part "RESISTOR_Dup1"))
    )
    (comp (ref "R8411")
      (value "*")
      (footprint "R0402")
      (description "НЁУГєсД¤µзЧи,10K,+/-5%,R0402,1/16W.")
      (fields
        (field (name "PCB FOOTPRINT") "R0402")
        (field (name "TOLERANCE") "5%")
        (field (name "OPTION") "DNP")
        (field (name "MANUFACTURER") "YAGEO")
        (field (name "ALTIUM_UNNAMED_1") "10K")
        (field (name "CREATED BY") "YTL")
      )
      (libsource (lib "*") (part "RESISTOR_Dup1"))
    )
    (comp (ref "R8412")
      (value "*")
      (footprint "R0402")
      (description "НЁУГєсД¤µзЧи,10K,+/-5%,R0402,1/16W.")
      (fields
        (field (name "PCB FOOTPRINT") "R0402")
        (field (name "TOLERANCE") "5%")
        (field (name "MANUFACTURER") "YAGEO")
        (field (name "ALTIUM_UNNAMED_1") "10K")
        (field (name "CREATED BY") "YTL")
      )
      (libsource (lib "*") (part "RESISTOR_Dup1"))
    )
    (comp (ref "R8413")
      (value "*")
      (footprint "R0402")
      (description "НЁУГєсД¤µзЧи,10K,+/-5%,R0402,1/16W.")
      (fields
        (field (name "PCB FOOTPRINT") "R0402")
        (field (name "TOLERANCE") "5%")
        (field (name "MANUFACTURER") "YAGEO")
        (field (name "OPTION") "DNP")
        (field (name "ALTIUM_UNNAMED_1") "10K")
        (field (name "CREATED BY") "YTL")
      )
      (libsource (lib "*") (part "RESISTOR_Dup1"))
    )
    (comp (ref "R8414")
      (value "*")
      (footprint "R0402")
      (description "НЁУГєсД¤µзЧи,22R,+/-5%,R0402,1/16W.")
      (fields
        (field (name "PCB FOOTPRINT") "R0402")
        (field (name "TOLERANCE") "5%")
        (field (name "MANUFACTURER") "YAGEO")
        (field (name "ALTIUM_UNNAMED_1") "22R")
        (field (name "CREATED BY") "YTL")
      )
      (libsource (lib "*") (part "RESISTOR_Dup1"))
    )
    (comp (ref "R8415")
      (value "*")
      (footprint "R0402")
      (description "НЁУГєсД¤µзЧи,33R,+/-5%,R0201,1/20W.")
      (fields
        (field (name "PCB FOOTPRINT") "R0201")
        (field (name "TOLERANCE") "5%")
        (field (name "MANUFACTURER") "YAGEO")
        (field (name "ALTIUM_UNNAMED_1") "33R")
        (field (name "CREATED BY") "YTL")
      )
      (libsource (lib "*") (part "RESISTOR_Dup1"))
    )
    (comp (ref "R8416")
      (value "*")
      (footprint "R0402")
      (description "НЁУГєсД¤µзЧи,33R,+/-5%,R0201,1/20W.")
      (fields
        (field (name "PCB FOOTPRINT") "R0201")
        (field (name "TOLERANCE") "5%")
        (field (name "MANUFACTURER") "YAGEO")
        (field (name "ALTIUM_UNNAMED_1") "33R")
        (field (name "CREATED BY") "YTL")
      )
      (libsource (lib "*") (part "RESISTOR_Dup1"))
    )
    (comp (ref "R8417")
      (value "*")
      (footprint "R0402")
      (description "НЁУГєсД¤µзЧи,10K,+/-5%,R0402,1/16W.")
      (fields
        (field (name "PCB FOOTPRINT") "R0402")
        (field (name "TOLERANCE") "5%")
        (field (name "MANUFACTURER") "YAGEO")
        (field (name "ALTIUM_UNNAMED_1") "10K")
        (field (name "CREATED BY") "YTL")
      )
      (libsource (lib "*") (part "RESISTOR_Dup1"))
    )
    (comp (ref "R8418")
      (value "*")
      (footprint "R0402")
      (description "НЁУГєсД¤µзЧи,49R9,+/-1%,R0201,1/20W.")
      (fields
        (field (name "PCB FOOTPRINT") "R0201")
        (field (name "TOLERANCE") "1%")
        (field (name "MANUFACTURER") "YAGEO")
        (field (name "ALTIUM_UNNAMED_1") "49.9R")
        (field (name "CREATED BY") "YTL")
      )
      (libsource (lib "*") (part "RESISTOR_Dup1"))
    )
    (comp (ref "R8419")
      (value "*")
      (footprint "R0402")
      (description "НЁУГєсД¤µзЧи,49R9,+/-1%,R0201,1/20W.")
      (fields
        (field (name "PCB FOOTPRINT") "R0201")
        (field (name "TOLERANCE") "1%")
        (field (name "MANUFACTURER") "YAGEO")
        (field (name "ALTIUM_UNNAMED_1") "49.9R")
        (field (name "CREATED BY") "YTL")
      )
      (libsource (lib "*") (part "RESISTOR_Dup1"))
    )
    (comp (ref "R8420")
      (value "*")
      (footprint "R0402")
      (description "НЁУГєсД¤µзЧи,4K7,+/-5%,R0402,1/16W.")
      (fields
        (field (name "PCB FOOTPRINT") "R0402")
        (field (name "TOLERANCE") "5%")
        (field (name "MANUFACTURER") "YAGEO")
        (field (name "ALTIUM_UNNAMED_1") "4.7K")
        (field (name "CREATED BY") "YTL")
      )
      (libsource (lib "*") (part "RESISTOR_Dup1"))
    )
    (comp (ref "R8421")
      (value "*")
      (footprint "R0402")
      (description "НЁУГєсД¤µзЧи,470R,+/-1%,R0402,1/16W.")
      (fields
        (field (name "PCB FOOTPRINT") "R0402")
        (field (name "TOLERANCE") "1%")
        (field (name "MANUFACTURER") "YAGEO")
        (field (name "ALTIUM_UNNAMED_1") "470R")
        (field (name "CREATED BY") "YTL")
      )
      (libsource (lib "*") (part "RESISTOR_Dup1"))
    )
    (comp (ref "R8422")
      (value "*")
      (footprint "R0402")
      (description "НЁУГєсД¤µзЧи,2R2,+/-5%,R0402,1/16W.")
      (fields
        (field (name "PCB FOOTPRINT") "R0402")
        (field (name "TOLERANCE") "5%")
        (field (name "MANUFACTURER") "YAGEO")
        (field (name "ALTIUM_UNNAMED_1") "2.2R")
        (field (name "CREATED BY") "YTL")
      )
      (libsource (lib "*") (part "RESISTOR_Dup1"))
    )
    (comp (ref "R8423")
      (value "*")
      (footprint "R0402")
      (description "НЁУГєсД¤µзЧи,33R,+/-5%,R0201,1/20W.")
      (fields
        (field (name "PCB FOOTPRINT") "R0201")
        (field (name "TOLERANCE") "5%")
        (field (name "MANUFACTURER") "YAGEO")
        (field (name "ALTIUM_UNNAMED_1") "33R")
        (field (name "CREATED BY") "YTL")
      )
      (libsource (lib "*") (part "RESISTOR_Dup1"))
    )
    (comp (ref "R8424")
      (value "*")
      (footprint "R0402")
      (description "НЁУГєсД¤µзЧи,33R,+/-5%,R0201,1/20W.")
      (fields
        (field (name "PCB FOOTPRINT") "R0201")
        (field (name "TOLERANCE") "5%")
        (field (name "MANUFACTURER") "YAGEO")
        (field (name "ALTIUM_UNNAMED_1") "33R")
        (field (name "CREATED BY") "YTL")
      )
      (libsource (lib "*") (part "RESISTOR_Dup1"))
    )
    (comp (ref "R8425")
      (value "*")
      (footprint "R0402")
      (description "НЁУГєсД¤µзЧи,49R9,+/-1%,R0201,1/20W.")
      (fields
        (field (name "PCB FOOTPRINT") "R0201")
        (field (name "TOLERANCE") "1%")
        (field (name "MANUFACTURER") "YAGEO")
        (field (name "ALTIUM_UNNAMED_1") "49.9R")
        (field (name "CREATED BY") "YTL")
      )
      (libsource (lib "*") (part "RESISTOR_Dup1"))
    )
    (comp (ref "R8426")
      (value "*")
      (footprint "R0402")
      (description "НЁУГєсД¤µзЧи,49R9,+/-1%,R0201,1/20W.")
      (fields
        (field (name "PCB FOOTPRINT") "R0201")
        (field (name "TOLERANCE") "1%")
        (field (name "MANUFACTURER") "YAGEO")
        (field (name "ALTIUM_UNNAMED_1") "49.9R")
        (field (name "CREATED BY") "YTL")
      )
      (libsource (lib "*") (part "RESISTOR_Dup1"))
    )
    (comp (ref "R8427")
      (value "*")
      (footprint "R0402")
      (description "НЁУГєсД¤µзЧи,100K,+/-5%,R0402,1/16W.")
      (fields
        (field (name "PCB FOOTPRINT") "R0402")
        (field (name "TOLERANCE") "5%")
        (field (name "MANUFACTURER") "YAGEO")
        (field (name "ALTIUM_UNNAMED_1") "100K")
        (field (name "CREATED BY") "YTL")
      )
      (libsource (lib "*") (part "RESISTOR_Dup1"))
    )
    (comp (ref "R8428")
      (value "*")
      (footprint "R0402")
      (description "НЁУГєсД¤µзЧи,100K,+/-5%,R0402,1/16W.")
      (fields
        (field (name "PCB FOOTPRINT") "R0402")
        (field (name "TOLERANCE") "5%")
        (field (name "MANUFACTURER") "YAGEO")
        (field (name "ALTIUM_UNNAMED_1") "100K")
        (field (name "CREATED BY") "YTL")
      )
      (libsource (lib "*") (part "RESISTOR_Dup1"))
    )
    (comp (ref "R8429")
      (value "*")
      (footprint "R0402")
      (description "НЁУГєсД¤µзЧи,10K,+/-5%,R0402,1/16W.")
      (fields
        (field (name "PCB FOOTPRINT") "R0402")
        (field (name "TOLERANCE") "5%")
        (field (name "MANUFACTURER") "YAGEO")
        (field (name "ALTIUM_UNNAMED_1") "10K")
        (field (name "CREATED BY") "YTL")
      )
      (libsource (lib "*") (part "RESISTOR_Dup1"))
    )
    (comp (ref "R8430")
      (value "*")
      (footprint "R0402")
      (description "НЁУГєсД¤µзЧи,232K,+/-1%,R0402,1/16W.")
      (fields
        (field (name "PCB FOOTPRINT") "R0402")
        (field (name "TOLERANCE") "1%")
        (field (name "MANUFACTURER") "YAGEO")
        (field (name "ALTIUM_UNNAMED_1") "232K")
        (field (name "CREATED BY") "YTL")
      )
      (libsource (lib "*") (part "RESISTOR_Dup1"))
    )
    (comp (ref "R8431")
      (value "*")
      (footprint "R0402")
      (description "Did Not Place.")
      (fields
        (field (name "PCB FOOTPRINT") "R0402")
        (field (name "ALTIUM_UNNAMED_1") "DNP")
        (field (name "CREATED BY") "JJJ")
      )
      (libsource (lib "*") (part "RESISTOR_Dup1"))
    )
    (comp (ref "R8432")
      (value "*")
      (footprint "R0402")
      (description "НЁУГєсД¤µзЧи,10K,+/-5%,R0402,1/16W.")
      (fields
        (field (name "PCB FOOTPRINT") "R0402")
        (field (name "TOLERANCE") "5%")
        (field (name "MANUFACTURER") "YAGEO")
        (field (name "ALTIUM_UNNAMED_1") "10K")
        (field (name "CREATED BY") "YTL")
      )
      (libsource (lib "*") (part "RESISTOR_Dup1"))
    )
    (comp (ref "R8433")
      (value "*")
      (footprint "R0402")
      (description "НЁУГєсД¤µзЧи,49K9,+/-1%,R0402,1/16W.")
      (fields
        (field (name "PCB FOOTPRINT") "R0402")
        (field (name "TOLERANCE") "1%")
        (field (name "MANUFACTURER") "YAGEO")
        (field (name "ALTIUM_UNNAMED_1") "49.9K")
        (field (name "CREATED BY") "YTL")
      )
      (libsource (lib "*") (part "RESISTOR_Dup1"))
    )
    (comp (ref "R8434")
      (value "*")
      (footprint "R0402")
      (description "НЁУГєсД¤µзЧи,10K,+/-5%,R0402,1/16W.")
      (fields
        (field (name "PCB FOOTPRINT") "R0402")
        (field (name "TOLERANCE") "5%")
        (field (name "MANUFACTURER") "YAGEO")
        (field (name "ALTIUM_UNNAMED_1") "10K")
        (field (name "CREATED BY") "YTL")
      )
      (libsource (lib "*") (part "RESISTOR_Dup1"))
    )
    (comp (ref "R8435")
      (value "*")
      (footprint "R0402")
      (description "НЁУГєсД¤µзЧи,51K,+/-5%,R0402,1/16W.")
      (fields
        (field (name "PCB FOOTPRINT") "R0402")
        (field (name "TOLERANCE") "5%")
        (field (name "MANUFACTURER") "YAGEO")
        (field (name "ALTIUM_UNNAMED_1") "51K")
        (field (name "CREATED BY") "YTL")
      )
      (libsource (lib "*") (part "RESISTOR_Dup1"))
    )
    (comp (ref "U8400")
      (value "*")
      (footprint "TSSOP20")
      (fields
        (field (name "PCB FOOTPRINT") "TSSOP20_6R50x4R40x1R20")
        (field (name "ALTIUM_UNNAMED_1") "PI6C557-05BLE")
      )
      (libsource (lib "*") (part "PI6C557-05BLE_0"))
    )
    (comp (ref "U8401")
      (value "*")
      (footprint "SOT_23_5")
      (description "High-PSRR 600mA LDO.Output3.3V.")
      (fields
        (field (name "PCB FOOTPRINT") "SOT_23_5")
        (field (name "MANUFACTURER") "PowtechЈЁ»ЄИуОщНюЈ©")
        (field (name "ALTIUM_UNNAMED_1") "PT5108E23E-33")
        (field (name "CREATED BY") "JJJ")
      )
      (libsource (lib "*") (part "LDO_PT5108"))
    )
    (comp (ref "U8402")
      (value "*")
      (footprint "SOT_23_6")
      (fields
        (field (name "PCB FOOTPRINT") "SOT_23_6")
        (field (name "MANUFACTURER") "SilergyЈЁОщБ¦ЅЬЈ©")
        (field (name "ALTIUM_UNNAMED_1") "SY8113B/SM8103ADC")
        (field (name "CREATED BY") "JJJ")
      )
      (libsource (lib "*") (part "DCDC_SY8113"))
    )
    (comp (ref "Y8400")
      (value "*")
      (footprint "CRY-3225")
      (description "ОЮФґѕ§ХсЈ¬25MЈ¬3225,ЎА10ppmЈ¬10pFЈ¬Hosonic")
      (fields
        (field (name "PCB FOOTPRINT") "CRY4_3R20X2R50X0R80")
        (field (name "MANUFACTURER") "Hosonic(єиРЗµзЧУ)")
        (field (name "ALTIUM_UNNAMED_1") "25MHz")
        (field (name "CREATED BY") "JJJ")
      )
      (libsource (lib "*") (part "CRYSTAL_4P"))
    )
  )
  (nets
    (net (code "1") (name "/PCIE30X4_CLKREQn_3V3_L") (class "Default")
      (node (ref "J8400") (pin "B12") (pinfunction "RSVD_B12_B12") (pintype "passive"))
      (node (ref "R8400") (pin "2") (pinfunction "2_2") (pintype "passive"))
    )
    (net (code "2") (name "/PCIE30X4_PERSTn_3V3_L") (class "Default")
      (node (ref "C8400") (pin "1") (pinfunction "1_1") (pintype "passive"))
      (node (ref "J8400") (pin "A11") (pinfunction "PERST#_A11") (pintype "passive"))
      (node (ref "R8402") (pin "2") (pinfunction "2_2") (pintype "passive"))
    )
    (net (code "3") (name "/PCIE30X4_PRSNT_3V3_L") (class "Default")
      (node (ref "J8400") (pin "B17") (pinfunction "PRSNT2#_1_B17") (pintype "passive"))
      (node (ref "J8400") (pin "B31") (pinfunction "PRSNT2#_2_B31") (pintype "passive"))
      (node (ref "R8403") (pin "2") (pinfunction "2_2") (pintype "passive"))
    )
    (net (code "4") (name "/PCIE30X4_REFCLKN_CON") (class "Default")
      (node (ref "J8400") (pin "A14") (pinfunction "REFCLK-_A14") (pintype "passive"))
      (node (ref "R8405") (pin "2") (pinfunction "2_2") (pintype "passive"))
      (node (ref "R8406") (pin "1") (pinfunction "1_1") (pintype "passive"))
    )
    (net (code "5") (name "/PCIE30X4_REFCLKP_CON") (class "Default")
      (node (ref "J8400") (pin "A13") (pinfunction "REFCLK+_A13") (pintype "passive"))
      (node (ref "R8404") (pin "2") (pinfunction "2_2") (pintype "passive"))
      (node (ref "R8407") (pin "1") (pinfunction "1_1") (pintype "passive"))
    )
    (net (code "6") (name "/PCIE30X4_WAKEn_3V3_L") (class "Default")
      (node (ref "J8400") (pin "B11") (pinfunction "WAKE#_B11") (pintype "passive"))
      (node (ref "R8401") (pin "2") (pinfunction "2_2") (pintype "passive"))
    )
    (net (code "7") (name "/PCIE30_TX0_N") (class "Default")
      (node (ref "C8402") (pin "2") (pinfunction "2_2") (pintype "passive"))
      (node (ref "J8400") (pin "B15") (pinfunction "PETn0_B15") (pintype "passive"))
    )
    (net (code "8") (name "/PCIE30_TX0_P") (class "Default")
      (node (ref "C8401") (pin "2") (pinfunction "2_2") (pintype "passive"))
      (node (ref "J8400") (pin "B14") (pinfunction "PETp0_B14") (pintype "passive"))
    )
    (net (code "9") (name "/PCIE30_TX1_N") (class "Default")
      (node (ref "C8404") (pin "2") (pinfunction "2_2") (pintype "passive"))
      (node (ref "J8400") (pin "B20") (pinfunction "PETn1_B20") (pintype "passive"))
    )
    (net (code "10") (name "/PCIE30_TX1_P") (class "Default")
      (node (ref "C8403") (pin "2") (pinfunction "2_2") (pintype "passive"))
      (node (ref "J8400") (pin "B19") (pinfunction "PETp1_B19") (pintype "passive"))
    )
    (net (code "11") (name "/PCIE30_TX2_N") (class "Default")
      (node (ref "C8406") (pin "2") (pinfunction "2_2") (pintype "passive"))
      (node (ref "J8400") (pin "B24") (pinfunction "PETn2_B24") (pintype "passive"))
    )
    (net (code "12") (name "/PCIE30_TX2_P") (class "Default")
      (node (ref "C8405") (pin "2") (pinfunction "2_2") (pintype "passive"))
      (node (ref "J8400") (pin "B23") (pinfunction "PETp2_B23") (pintype "passive"))
    )
    (net (code "13") (name "/PCIE30_TX3_N") (class "Default")
      (node (ref "C8408") (pin "2") (pinfunction "2_2") (pintype "passive"))
      (node (ref "J8400") (pin "B28") (pinfunction "PETn3_B28") (pintype "passive"))
    )
    (net (code "14") (name "/PCIE30_TX3_P") (class "Default")
      (node (ref "C8407") (pin "2") (pinfunction "2_2") (pintype "passive"))
      (node (ref "J8400") (pin "B27") (pinfunction "PETp3_B27") (pintype "passive"))
    )
    (net (code "15") (name "/PI6C_05_CLK0N") (class "Default")
      (node (ref "R8405") (pin "1") (pinfunction "1_1") (pintype "passive"))
      (node (ref "U8400") (pin "19") (pinfunction "CLK0N_19") (pintype "passive"))
    )
    (net (code "16") (name "/PI6C_05_CLK0P") (class "Default")
      (node (ref "R8404") (pin "1") (pinfunction "1_1") (pintype "passive"))
      (node (ref "U8400") (pin "20") (pinfunction "CLK0P_20") (pintype "passive"))
    )
    (net (code "17") (name "/PI6C_05_CLK2N") (class "Default")
      (node (ref "R8416") (pin "1") (pinfunction "1_1") (pintype "passive"))
      (node (ref "U8400") (pin "13") (pinfunction "CLK2N_13") (pintype "passive"))
    )
    (net (code "18") (name "/PI6C_05_CLK2P") (class "Default")
      (node (ref "R8415") (pin "1") (pinfunction "1_1") (pintype "passive"))
      (node (ref "U8400") (pin "14") (pinfunction "CLK2P_14") (pintype "passive"))
    )
    (net (code "19") (name "/PI6C_05_CLK3N") (class "Default")
      (node (ref "R8424") (pin "1") (pinfunction "1_1") (pintype "passive"))
      (node (ref "U8400") (pin "11") (pinfunction "CLK3N_11") (pintype "passive"))
    )
    (net (code "20") (name "/PI6C_05_CLK3P") (class "Default")
      (node (ref "R8423") (pin "1") (pinfunction "1_1") (pintype "passive"))
      (node (ref "U8400") (pin "12") (pinfunction "CLK3P_12") (pintype "passive"))
    )
    (net (code "21") (name "/PI6C_05_OE") (class "Default")
      (node (ref "R8417") (pin "2") (pinfunction "2_2") (pintype "passive"))
      (node (ref "U8400") (pin "8") (pinfunction "OE_8") (pintype "passive"))
    )
    (net (code "22") (name "/PI6C_05_PDn") (class "Default")
      (node (ref "R8420") (pin "2") (pinfunction "2_2") (pintype "passive"))
      (node (ref "U8400") (pin "7") (pinfunction "PDn_7") (pintype "passive"))
    )
    (net (code "23") (name "/PI6C_05_S0") (class "Default")
      (node (ref "R8410") (pin "2") (pinfunction "2_2") (pintype "passive"))
      (node (ref "R8411") (pin "1") (pinfunction "1_1") (pintype "passive"))
      (node (ref "U8400") (pin "2") (pinfunction "S0_2") (pintype "passive"))
    )
    (net (code "24") (name "/PI6C_05_S1") (class "Default")
      (node (ref "R8412") (pin "2") (pinfunction "2_2") (pintype "passive"))
      (node (ref "R8413") (pin "1") (pinfunction "1_1") (pintype "passive"))
      (node (ref "U8400") (pin "3") (pinfunction "S1_3") (pintype "passive"))
    )
    (net (code "25") (name "/PI6C_05_S2") (class "Default")
      (node (ref "R8408") (pin "2") (pinfunction "2_2") (pintype "passive"))
      (node (ref "R8409") (pin "1") (pinfunction "1_1") (pintype "passive"))
      (node (ref "U8400") (pin "4") (pinfunction "S2_4") (pintype "passive"))
    )
    (net (code "26") (name "GND") (class "Default")
      (node (ref "C8400") (pin "2") (pinfunction "2_2") (pintype "passive"))
      (node (ref "C8409") (pin "2") (pinfunction "2_2") (pintype "passive"))
      (node (ref "C8410") (pin "2") (pinfunction "2_2") (pintype "passive"))
      (node (ref "C8411") (pin "2") (pinfunction "2_2") (pintype "passive"))
      (node (ref "C8412") (pin "2") (pinfunction "2_2") (pintype "passive"))
      (node (ref "C8413") (pin "2") (pinfunction "2_2") (pintype "passive"))
      (node (ref "C8414") (pin "2") (pinfunction "2_2") (pintype "passive"))
      (node (ref "C8415") (pin "2") (pinfunction "2_2") (pintype "passive"))
      (node (ref "C8416") (pin "2") (pinfunction "2_2") (pintype "passive"))
      (node (ref "C8417") (pin "2") (pinfunction "2_2") (pintype "passive"))
      (node (ref "C8418") (pin "2") (pinfunction "2_2") (pintype "passive"))
      (node (ref "C8419") (pin "2") (pinfunction "2_2") (pintype "passive"))
      (node (ref "C8420") (pin "2") (pinfunction "2_2") (pintype "passive"))
      (node (ref "C8421") (pin "2") (pinfunction "2_2") (pintype "passive"))
      (node (ref "C8422") (pin "2") (pinfunction "2_2") (pintype "passive"))
      (node (ref "C8423") (pin "2") (pinfunction "2_2") (pintype "passive"))
      (node (ref "C8424") (pin "2") (pinfunction "2_2") (pintype "passive"))
      (node (ref "C8425") (pin "2") (pinfunction "2_2") (pintype "passive"))
      (node (ref "C8426") (pin "2") (pinfunction "2_2") (pintype "passive"))
      (node (ref "C8427") (pin "2") (pinfunction "2_2") (pintype "passive"))
      (node (ref "C8429") (pin "2") (pinfunction "2_2") (pintype "passive"))
      (node (ref "C8431") (pin "2") (pinfunction "2_2") (pintype "passive"))
      (node (ref "C8432") (pin "2") (pinfunction "2_2") (pintype "passive"))
      (node (ref "C8433") (pin "2") (pinfunction "2_2") (pintype "passive"))
      (node (ref "C8435") (pin "2") (pinfunction "2_2") (pintype "passive"))
      (node (ref "C8436") (pin "2") (pinfunction "2_2") (pintype "passive"))
      (node (ref "C8437") (pin "2") (pinfunction "2_2") (pintype "passive"))
      (node (ref "J8400") (pin "1") (pinfunction "G1_1") (pintype "passive"))
      (node (ref "J8400") (pin "2") (pinfunction "G2_2") (pintype "passive"))
      (node (ref "J8400") (pin "A1") (pinfunction "PRSNT1#_A1") (pintype "passive"))
      (node (ref "J8400") (pin "A12") (pinfunction "GND_A12_A12") (pintype "passive"))
      (node (ref "J8400") (pin "A15") (pinfunction "GND_A15_A15") (pintype "passive"))
      (node (ref "J8400") (pin "A18") (pinfunction "GND_A18_A18") (pintype "passive"))
      (node (ref "J8400") (pin "A20") (pinfunction "GND_A20_A20") (pintype "passive"))
      (node (ref "J8400") (pin "A23") (pinfunction "GND_A23_A23") (pintype "passive"))
      (node (ref "J8400") (pin "A24") (pinfunction "GND_A24_A24") (pintype "passive"))
      (node (ref "J8400") (pin "A27") (pinfunction "GND_A27_A27") (pintype "passive"))
      (node (ref "J8400") (pin "A28") (pinfunction "GND_A28_A28") (pintype "passive"))
      (node (ref "J8400") (pin "A31") (pinfunction "GND_A31_A31") (pintype "passive"))
      (node (ref "J8400") (pin "A4") (pinfunction "GND_A4_A4") (pintype "passive"))
      (node (ref "J8400") (pin "B13") (pinfunction "GND_B13_B13") (pintype "passive"))
      (node (ref "J8400") (pin "B16") (pinfunction "GND_B16_B16") (pintype "passive"))
      (node (ref "J8400") (pin "B18") (pinfunction "GND_B18_B18") (pintype "passive"))
      (node (ref "J8400") (pin "B21") (pinfunction "GND_B21_B21") (pintype "passive"))
      (node (ref "J8400") (pin "B22") (pinfunction "GND_B22_B22") (pintype "passive"))
      (node (ref "J8400") (pin "B25") (pinfunction "GND_B25_B25") (pintype "passive"))
      (node (ref "J8400") (pin "B26") (pinfunction "GND_B26_B26") (pintype "passive"))
      (node (ref "J8400") (pin "B29") (pinfunction "GND_B29_B29") (pintype "passive"))
      (node (ref "J8400") (pin "B32") (pinfunction "GND_B32_B32") (pintype "passive"))
      (node (ref "J8400") (pin "B4") (pinfunction "GND_B4_B4") (pintype "passive"))
      (node (ref "J8400") (pin "B7") (pinfunction "GND_B7_B7") (pintype "passive"))
      (node (ref "Q8401") (pin "2") (pinfunction "EMITTER_2") (pintype "passive"))
      (node (ref "R8406") (pin "2") (pinfunction "2_2") (pintype "passive"))
      (node (ref "R8407") (pin "2") (pinfunction "2_2") (pintype "passive"))
      (node (ref "R8409") (pin "2") (pinfunction "2_2") (pintype "passive"))
      (node (ref "R8411") (pin "2") (pinfunction "2_2") (pintype "passive"))
      (node (ref "R8413") (pin "2") (pinfunction "2_2") (pintype "passive"))
      (node (ref "R8418") (pin "2") (pinfunction "2_2") (pintype "passive"))
      (node (ref "R8419") (pin "2") (pinfunction "2_2") (pintype "passive"))
      (node (ref "R8421") (pin "2") (pinfunction "2_2") (pintype "passive"))
      (node (ref "R8425") (pin "2") (pinfunction "2_2") (pintype "passive"))
      (node (ref "R8426") (pin "2") (pinfunction "2_2") (pintype "passive"))
      (node (ref "R8431") (pin "2") (pinfunction "2_2") (pintype "passive"))
      (node (ref "R8433") (pin "2") (pinfunction "2_2") (pintype "passive"))
      (node (ref "R8435") (pin "2") (pinfunction "2_2") (pintype "passive"))
      (node (ref "U8400") (pin "16") (pinfunction "GNDODA_16") (pintype "passive"))
      (node (ref "U8400") (pin "9") (pinfunction "GNDXD_9") (pintype "passive"))
      (node (ref "U8401") (pin "2") (pinfunction "GND_2") (pintype "passive"))
      (node (ref "U8402") (pin "2") (pinfunction "GND_2") (pintype "passive"))
      (node (ref "Y8400") (pin "2") (pinfunction "GND_2") (pintype "power_in"))
      (node (ref "Y8400") (pin "4") (pinfunction "GND_4") (pintype "power_in"))
    )
    (net (code "27") (name "Net-(Q8400-GATE)") (class "Default")
      (node (ref "C8430") (pin "2") (pinfunction "2_2") (pintype "passive"))
      (node (ref "Q8400") (pin "1") (pinfunction "GATE_1") (pintype "passive"))
      (node (ref "R8428") (pin "2") (pinfunction "2_2") (pintype "passive"))
      (node (ref "R8432") (pin "1") (pinfunction "1_1") (pintype "passive"))
    )
    (net (code "28") (name "Net-(Q8401-BASE)") (class "Default")
      (node (ref "Q8401") (pin "1") (pinfunction "BASE_1") (pintype "passive"))
      (node (ref "R8434") (pin "2") (pinfunction "2_2") (pintype "passive"))
      (node (ref "R8435") (pin "1") (pinfunction "1_1") (pintype "passive"))
    )
    (net (code "29") (name "Net-(Q8401-COLLECTOR)") (class "Default")
      (node (ref "Q8401") (pin "3") (pinfunction "COLLECTOR_3") (pintype "passive"))
      (node (ref "R8432") (pin "2") (pinfunction "2_2") (pintype "passive"))
    )
    (net (code "30") (name "Net-(U8400-IREF)") (class "Default")
      (node (ref "R8421") (pin "1") (pinfunction "1_1") (pintype "passive"))
      (node (ref "U8400") (pin "10") (pinfunction "IREF_10") (pintype "passive"))
    )
    (net (code "31") (name "Net-(U8400-X1)") (class "Default")
      (node (ref "C8419") (pin "1") (pinfunction "1_1") (pintype "passive"))
      (node (ref "U8400") (pin "5") (pinfunction "X1_5") (pintype "passive"))
      (node (ref "Y8400") (pin "1") (pinfunction "X1_1") (pintype "passive"))
    )
    (net (code "32") (name "Net-(U8400-X2)") (class "Default")
      (node (ref "R8414") (pin "2") (pinfunction "2_2") (pintype "passive"))
      (node (ref "U8400") (pin "6") (pinfunction "X2_6") (pintype "passive"))
    )
    (net (code "33") (name "Net-(U8401-BP)") (class "Default")
      (node (ref "C8427") (pin "1") (pinfunction "1_1") (pintype "passive"))
      (node (ref "U8401") (pin "4") (pinfunction "BP_4") (pintype "passive"))
    )
    (net (code "34") (name "Net-(U8401-EN)") (class "Default")
      (node (ref "C8426") (pin "1") (pinfunction "1_1") (pintype "passive"))
      (node (ref "R8427") (pin "2") (pinfunction "2_2") (pintype "passive"))
      (node (ref "U8401") (pin "3") (pinfunction "EN_3") (pintype "passive"))
    )
    (net (code "35") (name "Net-(U8402-BS)") (class "Default")
      (node (ref "C8428") (pin "1") (pinfunction "1_1") (pintype "passive"))
      (node (ref "U8402") (pin "1") (pinfunction "BS_1") (pintype "passive"))
    )
    (net (code "36") (name "Net-(U8402-EN)") (class "Default")
      (node (ref "R8429") (pin "2") (pinfunction "2_2") (pintype "passive"))
      (node (ref "R8431") (pin "1") (pinfunction "1_1") (pintype "passive"))
      (node (ref "U8402") (pin "4") (pinfunction "EN_4") (pintype "passive"))
    )
    (net (code "37") (name "Net-(U8402-FB{slash}OUT)") (class "Default")
      (node (ref "C8434") (pin "2") (pinfunction "2_2") (pintype "passive"))
      (node (ref "R8430") (pin "2") (pinfunction "2_2") (pintype "passive"))
      (node (ref "R8433") (pin "1") (pinfunction "1_1") (pintype "passive"))
      (node (ref "U8402") (pin "3") (pinfunction "FB/OUT_3") (pintype "passive"))
    )
    (net (code "38") (name "Net-(U8402-LX)") (class "Default")
      (node (ref "C8428") (pin "2") (pinfunction "2_2") (pintype "passive"))
      (node (ref "L8400") (pin "1") (pinfunction "1_1") (pintype "passive"))
      (node (ref "U8402") (pin "6") (pinfunction "LX_6") (pintype "passive"))
    )
    (net (code "39") (name "Net-(Y8400-X2)") (class "Default")
      (node (ref "C8420") (pin "1") (pinfunction "1_1") (pintype "passive"))
      (node (ref "R8414") (pin "1") (pinfunction "1_1") (pintype "passive"))
      (node (ref "Y8400") (pin "3") (pinfunction "X2_3") (pintype "passive"))
    )
    (net (code "40") (name "PCIE30X4_CLKREQn_M1_L") (class "Default")
      (node (ref "R8400") (pin "1") (pinfunction "1_1") (pintype "passive"))
    )
    (net (code "41") (name "PCIE30X4_PERSTn_M1_L") (class "Default")
      (node (ref "R8402") (pin "1") (pinfunction "1_1") (pintype "passive"))
    )
    (net (code "42") (name "PCIE30X4_PRSNT_L_GPIO3_C7") (class "Default")
      (node (ref "R8403") (pin "1") (pinfunction "1_1") (pintype "passive"))
    )
    (net (code "43") (name "PCIE30X4_WAKEn_M1_L") (class "Default")
      (node (ref "R8401") (pin "1") (pinfunction "1_1") (pintype "passive"))
    )
    (net (code "44") (name "PCIE30_PORT0_REFCLKN_IN") (class "Default")
      (node (ref "R8416") (pin "2") (pinfunction "2_2") (pintype "passive"))
      (node (ref "R8418") (pin "1") (pinfunction "1_1") (pintype "passive"))
    )
    (net (code "45") (name "PCIE30_PORT0_REFCLKP_IN") (class "Default")
      (node (ref "R8415") (pin "2") (pinfunction "2_2") (pintype "passive"))
      (node (ref "R8419") (pin "1") (pinfunction "1_1") (pintype "passive"))
    )
    (net (code "46") (name "PCIE30_PORT0_RX0N") (class "Default")
      (node (ref "J8400") (pin "A17") (pinfunction "PERn0_A17") (pintype "passive"))
    )
    (net (code "47") (name "PCIE30_PORT0_RX0P") (class "Default")
      (node (ref "J8400") (pin "A16") (pinfunction "PERp0_A16") (pintype "passive"))
    )
    (net (code "48") (name "PCIE30_PORT0_RX1N") (class "Default")
      (node (ref "J8400") (pin "A22") (pinfunction "PERn1_A22") (pintype "passive"))
    )
    (net (code "49") (name "PCIE30_PORT0_RX1P") (class "Default")
      (node (ref "J8400") (pin "A21") (pinfunction "PERp1_A21") (pintype "passive"))
    )
    (net (code "50") (name "PCIE30_PORT0_TX0N") (class "Default")
      (node (ref "C8402") (pin "1") (pinfunction "1_1") (pintype "passive"))
    )
    (net (code "51") (name "PCIE30_PORT0_TX0P") (class "Default")
      (node (ref "C8401") (pin "1") (pinfunction "1_1") (pintype "passive"))
    )
    (net (code "52") (name "PCIE30_PORT0_TX1N") (class "Default")
      (node (ref "C8404") (pin "1") (pinfunction "1_1") (pintype "passive"))
    )
    (net (code "53") (name "PCIE30_PORT0_TX1P") (class "Default")
      (node (ref "C8403") (pin "1") (pinfunction "1_1") (pintype "passive"))
    )
    (net (code "54") (name "PCIE30_PORT1_REFCLKN_IN") (class "Default")
      (node (ref "R8424") (pin "2") (pinfunction "2_2") (pintype "passive"))
      (node (ref "R8425") (pin "1") (pinfunction "1_1") (pintype "passive"))
    )
    (net (code "55") (name "PCIE30_PORT1_REFCLKP_IN") (class "Default")
      (node (ref "R8423") (pin "2") (pinfunction "2_2") (pintype "passive"))
      (node (ref "R8426") (pin "1") (pinfunction "1_1") (pintype "passive"))
    )
    (net (code "56") (name "PCIE30_PORT1_RX2N") (class "Default")
      (node (ref "J8400") (pin "A26") (pinfunction "PERn2_A26") (pintype "passive"))
    )
    (net (code "57") (name "PCIE30_PORT1_RX2P") (class "Default")
      (node (ref "J8400") (pin "A25") (pinfunction "PERp2_A25") (pintype "passive"))
    )
    (net (code "58") (name "PCIE30_PORT1_RX3N") (class "Default")
      (node (ref "J8400") (pin "A30") (pinfunction "PERn3_A30") (pintype "passive"))
    )
    (net (code "59") (name "PCIE30_PORT1_RX3P") (class "Default")
      (node (ref "J8400") (pin "A29") (pinfunction "PERp3_A29") (pintype "passive"))
    )
    (net (code "60") (name "PCIE30_PORT1_TX2N") (class "Default")
      (node (ref "C8406") (pin "1") (pinfunction "1_1") (pintype "passive"))
    )
    (net (code "61") (name "PCIE30_PORT1_TX2P") (class "Default")
      (node (ref "C8405") (pin "1") (pinfunction "1_1") (pintype "passive"))
    )
    (net (code "62") (name "PCIE30_PORT1_TX3N") (class "Default")
      (node (ref "C8408") (pin "1") (pinfunction "1_1") (pintype "passive"))
    )
    (net (code "63") (name "PCIE30_PORT1_TX3P") (class "Default")
      (node (ref "C8407") (pin "1") (pinfunction "1_1") (pintype "passive"))
    )
    (net (code "64") (name "PCIE30x4_PWREN_H_GPIO3_D5") (class "Default")
      (node (ref "R8427") (pin "1") (pinfunction "1_1") (pintype "passive"))
      (node (ref "R8429") (pin "1") (pinfunction "1_1") (pintype "passive"))
      (node (ref "R8434") (pin "1") (pinfunction "1_1") (pintype "passive"))
    )
    (net (code "65") (name "VCC3V3_PCIE30") (class "Default")
      (node (ref "C8411") (pin "1") (pinfunction "1_1") (pintype "passive"))
      (node (ref "C8412") (pin "1") (pinfunction "1_1") (pintype "passive"))
      (node (ref "C8413") (pin "1") (pinfunction "1_1") (pintype "passive"))
      (node (ref "C8414") (pin "1") (pinfunction "1_1") (pintype "passive"))
      (node (ref "C8415") (pin "1") (pinfunction "1_1") (pintype "passive"))
      (node (ref "C8416") (pin "1") (pinfunction "1_1") (pintype "passive"))
      (node (ref "C8434") (pin "1") (pinfunction "1_1") (pintype "passive"))
      (node (ref "C8435") (pin "1") (pinfunction "1_1") (pintype "passive"))
      (node (ref "C8436") (pin "1") (pinfunction "1_1") (pintype "passive"))
      (node (ref "C8437") (pin "1") (pinfunction "1_1") (pintype "passive"))
      (node (ref "J8400") (pin "A10") (pinfunction "+3.3V_3_A10") (pintype "passive"))
      (node (ref "J8400") (pin "A9") (pinfunction "+3.3V_2_A9") (pintype "passive"))
      (node (ref "J8400") (pin "B10") (pinfunction "3.3VAUX_B10") (pintype "passive"))
      (node (ref "J8400") (pin "B8") (pinfunction "+3.3V_1_B8") (pintype "passive"))
      (node (ref "L8400") (pin "2") (pinfunction "2_2") (pintype "passive"))
      (node (ref "R8430") (pin "1") (pinfunction "1_1") (pintype "passive"))
    )
    (net (code "66") (name "VCC3V3_PI6C_05") (class "Default")
      (node (ref "C8417") (pin "1") (pinfunction "1_1") (pintype "passive"))
      (node (ref "C8418") (pin "1") (pinfunction "1_1") (pintype "passive"))
      (node (ref "C8422") (pin "1") (pinfunction "1_1") (pintype "passive"))
      (node (ref "C8425") (pin "1") (pinfunction "1_1") (pintype "passive"))
      (node (ref "R8408") (pin "1") (pinfunction "1_1") (pintype "passive"))
      (node (ref "R8410") (pin "1") (pinfunction "1_1") (pintype "passive"))
      (node (ref "R8412") (pin "1") (pinfunction "1_1") (pintype "passive"))
      (node (ref "R8417") (pin "1") (pinfunction "1_1") (pintype "passive"))
      (node (ref "R8420") (pin "1") (pinfunction "1_1") (pintype "passive"))
      (node (ref "R8422") (pin "1") (pinfunction "1_1") (pintype "passive"))
      (node (ref "U8400") (pin "1") (pinfunction "VDDXD_1") (pintype "passive"))
      (node (ref "U8401") (pin "5") (pinfunction "OUT_5") (pintype "passive"))
    )
    (net (code "67") (name "VCC4V0_SYS") (class "Default")
      (node (ref "C8421") (pin "1") (pinfunction "1_1") (pintype "passive"))
      (node (ref "U8401") (pin "1") (pinfunction "IN_1") (pintype "passive"))
    )
    (net (code "68") (name "VCC12V_DCIN") (class "Default")
      (node (ref "C8429") (pin "1") (pinfunction "1_1") (pintype "passive"))
      (node (ref "C8430") (pin "1") (pinfunction "1_1") (pintype "passive"))
      (node (ref "C8432") (pin "1") (pinfunction "1_1") (pintype "passive"))
      (node (ref "C8433") (pin "1") (pinfunction "1_1") (pintype "passive"))
      (node (ref "Q8400") (pin "2") (pinfunction "SOURCE_2") (pintype "passive"))
      (node (ref "R8428") (pin "1") (pinfunction "1_1") (pintype "passive"))
      (node (ref "U8402") (pin "5") (pinfunction "VIN_5") (pintype "passive"))
    )
    (net (code "69") (name "VCC12V_PCIE30") (class "Default")
      (node (ref "C8409") (pin "1") (pinfunction "1_1") (pintype "passive"))
      (node (ref "C8410") (pin "1") (pinfunction "1_1") (pintype "passive"))
      (node (ref "C8431") (pin "1") (pinfunction "1_1") (pintype "passive"))
      (node (ref "J8400") (pin "A2") (pinfunction "+12V_4_A2") (pintype "passive"))
      (node (ref "J8400") (pin "A3") (pinfunction "+12V_5_A3") (pintype "passive"))
      (node (ref "J8400") (pin "B1") (pinfunction "+12V_1_B1") (pintype "passive"))
      (node (ref "J8400") (pin "B2") (pinfunction "+12V_2_B2") (pintype "passive"))
      (node (ref "J8400") (pin "B3") (pinfunction "+12V_3_B3") (pintype "passive"))
      (node (ref "Q8400") (pin "3") (pinfunction "DRAIN_3") (pintype "passive"))
    )
    (net (code "70") (name "VCCA3V3_PI6C_05") (class "Default")
      (node (ref "C8423") (pin "1") (pinfunction "1_1") (pintype "passive"))
      (node (ref "C8424") (pin "1") (pinfunction "1_1") (pintype "passive"))
      (node (ref "R8422") (pin "2") (pinfunction "2_2") (pintype "passive"))
      (node (ref "U8400") (pin "15") (pinfunction "VDDODA_15") (pintype "passive"))
    )
    (net (code "71") (name "unconnected-(J8400-JTAG_TCK-PadA5)") (class "Default")
      (node (ref "J8400") (pin "A5") (pinfunction "JTAG_TCK_A5") (pintype "passive+no_connect"))
    )
    (net (code "72") (name "unconnected-(J8400-JTAG_TDI-PadA6)") (class "Default")
      (node (ref "J8400") (pin "A6") (pinfunction "JTAG_TDI_A6") (pintype "passive+no_connect"))
    )
    (net (code "73") (name "unconnected-(J8400-JTAG_TDO-PadA7)") (class "Default")
      (node (ref "J8400") (pin "A7") (pinfunction "JTAG_TDO_A7") (pintype "passive+no_connect"))
    )
    (net (code "74") (name "unconnected-(J8400-JTAG_TMS-PadA8)") (class "Default")
      (node (ref "J8400") (pin "A8") (pinfunction "JTAG_TMS_A8") (pintype "passive+no_connect"))
    )
    (net (code "75") (name "unconnected-(J8400-JTAG_TRST-PadB9)") (class "Default")
      (node (ref "J8400") (pin "B9") (pinfunction "JTAG_TRST_B9") (pintype "passive+no_connect"))
    )
    (net (code "76") (name "unconnected-(J8400-RSVD_A19-PadA19)") (class "Default")
      (node (ref "J8400") (pin "A19") (pinfunction "RSVD_A19_A19") (pintype "passive+no_connect"))
    )
    (net (code "77") (name "unconnected-(J8400-RSVD_A32-PadA32)") (class "Default")
      (node (ref "J8400") (pin "A32") (pinfunction "RSVD_A32_A32") (pintype "passive+no_connect"))
    )
    (net (code "78") (name "unconnected-(J8400-RSVD_B30-PadB30)") (class "Default")
      (node (ref "J8400") (pin "B30") (pinfunction "RSVD_B30_B30") (pintype "passive+no_connect"))
    )
    (net (code "79") (name "unconnected-(J8400-SMCLK-PadB5)") (class "Default")
      (node (ref "J8400") (pin "B5") (pinfunction "SMCLK_B5") (pintype "passive+no_connect"))
    )
    (net (code "80") (name "unconnected-(J8400-SMDAT-PadB6)") (class "Default")
      (node (ref "J8400") (pin "B6") (pinfunction "SMDAT_B6") (pintype "passive+no_connect"))
    )
    (net (code "81") (name "unconnected-(U8400-CLK1N-Pad17)") (class "Default")
      (node (ref "U8400") (pin "17") (pinfunction "CLK1N_17") (pintype "passive+no_connect"))
    )
    (net (code "82") (name "unconnected-(U8400-CLK1P-Pad18)") (class "Default")
      (node (ref "U8400") (pin "18") (pinfunction "CLK1P_18") (pintype "passive+no_connect"))
    )
  )
)
